# refSpoj.net
KiCad netlist of a schematic drawn in EAGLE
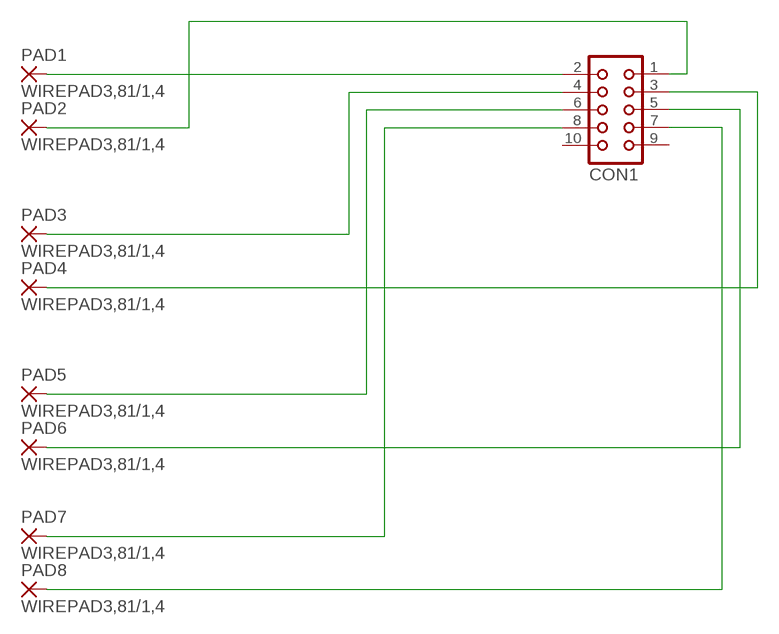
[diagram p0: schematic, sheet 1]

(export (version "E")
  (design (tool "Eeschema 10.0.6"))
  (components
    (comp (ref "CON1")
      (value "CON10")
      (footprint "eagle-import:CON10")
      (libsource (lib "eagle-import") (part "CON10"))
    )
    (comp (ref "PAD1")
      (value "WIREPAD3,81/1,4")
      (footprint "eagle-import:3,81_1,4")
      (libsource (lib "eagle-import") (part "WIREPAD3,81/1,4"))
    )
    (comp (ref "PAD2")
      (value "WIREPAD3,81/1,4")
      (footprint "eagle-import:3,81_1,4")
      (libsource (lib "eagle-import") (part "WIREPAD3,81/1,4"))
    )
    (comp (ref "PAD3")
      (value "WIREPAD3,81/1,4")
      (footprint "eagle-import:3,81_1,4")
      (libsource (lib "eagle-import") (part "WIREPAD3,81/1,4"))
    )
    (comp (ref "PAD4")
      (value "WIREPAD3,81/1,4")
      (footprint "eagle-import:3,81_1,4")
      (libsource (lib "eagle-import") (part "WIREPAD3,81/1,4"))
    )
    (comp (ref "PAD5")
      (value "WIREPAD3,81/1,4")
      (footprint "eagle-import:3,81_1,4")
      (libsource (lib "eagle-import") (part "WIREPAD3,81/1,4"))
    )
    (comp (ref "PAD6")
      (value "WIREPAD3,81/1,4")
      (footprint "eagle-import:3,81_1,4")
      (libsource (lib "eagle-import") (part "WIREPAD3,81/1,4"))
    )
    (comp (ref "PAD7")
      (value "WIREPAD3,81/1,4")
      (footprint "eagle-import:3,81_1,4")
      (libsource (lib "eagle-import") (part "WIREPAD3,81/1,4"))
    )
    (comp (ref "PAD8")
      (value "WIREPAD3,81/1,4")
      (footprint "eagle-import:3,81_1,4")
      (libsource (lib "eagle-import") (part "WIREPAD3,81/1,4"))
    )
  )
  (nets
    (net (code "1") (name "Net-(PAD1-P)") (class "Default")
      (node (ref "CON1") (pin "2") (pinfunction "2_2") (pintype "passive"))
      (node (ref "PAD1") (pin "1") (pinfunction "P_1") (pintype "passive"))
    )
    (net (code "2") (name "Net-(PAD2-P)") (class "Default")
      (node (ref "CON1") (pin "1") (pinfunction "1_1") (pintype "passive"))
      (node (ref "PAD2") (pin "1") (pinfunction "P_1") (pintype "passive"))
    )
    (net (code "3") (name "Net-(PAD3-P)") (class "Default")
      (node (ref "CON1") (pin "4") (pinfunction "4_4") (pintype "passive"))
      (node (ref "PAD3") (pin "1") (pinfunction "P_1") (pintype "passive"))
    )
    (net (code "4") (name "Net-(PAD4-P)") (class "Default")
      (node (ref "CON1") (pin "3") (pinfunction "3_3") (pintype "passive"))
      (node (ref "PAD4") (pin "1") (pinfunction "P_1") (pintype "passive"))
    )
    (net (code "5") (name "Net-(PAD5-P)") (class "Default")
      (node (ref "CON1") (pin "6") (pinfunction "6_6") (pintype "passive"))
      (node (ref "PAD5") (pin "1") (pinfunction "P_1") (pintype "passive"))
    )
    (net (code "6") (name "Net-(PAD6-P)") (class "Default")
      (node (ref "CON1") (pin "5") (pinfunction "5_5") (pintype "passive"))
      (node (ref "PAD6") (pin "1") (pinfunction "P_1") (pintype "passive"))
    )
    (net (code "7") (name "Net-(PAD7-P)") (class "Default")
      (node (ref "CON1") (pin "8") (pinfunction "8_8") (pintype "passive"))
      (node (ref "PAD7") (pin "1") (pinfunction "P_1") (pintype "passive"))
    )
    (net (code "8") (name "Net-(PAD8-P)") (class "Default")
      (node (ref "CON1") (pin "7") (pinfunction "7_7") (pintype "passive"))
      (node (ref "PAD8") (pin "1") (pinfunction "P_1") (pintype "passive"))
    )
    (net (code "9") (name "unconnected-(CON1-Pad9)") (class "Default")
      (node (ref "CON1") (pin "9") (pinfunction "9_9") (pintype "passive"))
    )
    (net (code "10") (name "unconnected-(CON1-Pad10)") (class "Default")
      (node (ref "CON1") (pin "10") (pinfunction "10_10") (pintype "passive"))
    )
  )
)
